# Driver.net
KiCad netlist of a schematic drawn in Altium Designer
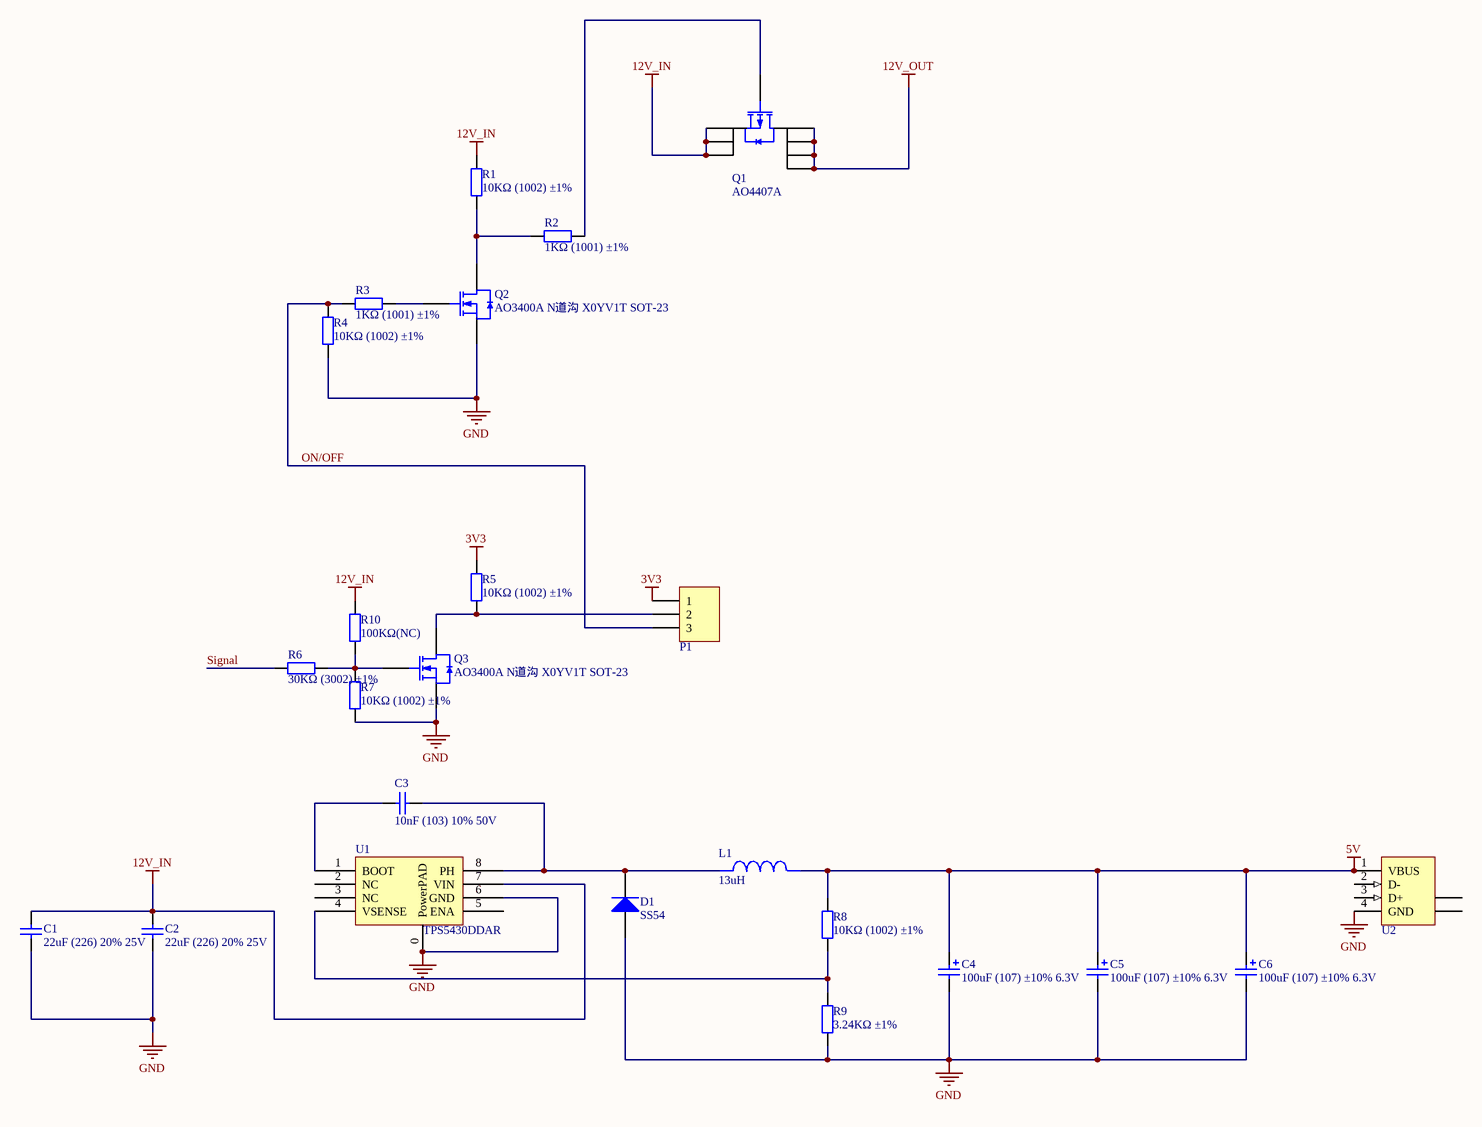
[diagram p0: Driver.SchDoc]

(export (version "E")
  (design (tool "Eeschema 10.0.6"))
  (components
    (comp (ref "C1")
      (value "22uF (226) 20% 25V")
      (footprint "0805_C")
      (description "贴片电容")
      (libsource (lib "Miscellaneous Devices LC") (part "0805 22uF (226) 20% 25V"))
    )
    (comp (ref "C2")
      (value "22uF (226) 20% 25V")
      (footprint "0805_C")
      (description "贴片电容")
      (libsource (lib "Miscellaneous Devices LC") (part "0805 22uF (226) 20% 25V"))
    )
    (comp (ref "C3")
      (value "10nF (103) 10% 50V")
      (footprint "0603_C")
      (description "贴片电容")
      (libsource (lib "Miscellaneous Devices LC") (part "0603 10nF (103) 10% 50V"))
    )
    (comp (ref "C4")
      (value "100uF (107) ±10% 6.3V")
      (footprint "CASE-B_3528")
      (description "钽电容")
      (libsource (lib "Miscellaneous Devices LC") (part "3528 100uF (107) 10% 6.3V"))
    )
    (comp (ref "C5")
      (value "100uF (107) ±10% 6.3V")
      (footprint "CASE-B_3528")
      (description "钽电容")
      (libsource (lib "Miscellaneous Devices LC") (part "3528 100uF (107) 10% 6.3V"))
    )
    (comp (ref "C6")
      (value "100uF (107) ±10% 6.3V")
      (footprint "CASE-B_3528")
      (description "钽电容")
      (libsource (lib "Miscellaneous Devices LC") (part "3528 100uF (107) 10% 6.3V"))
    )
    (comp (ref "D1")
      (value "SS54")
      (footprint "SMA(DO-214AC)_S1")
      (description "二极管")
      (libsource (lib "Miscellaneous Devices LC") (part "SMA(DO-214AC) SS54"))
    )
    (comp (ref "L1")
      (value "13uH")
      (footprint "WE-PDF-1045")
      (description "Unknown")
      (fields (field (name "MANUFACTURER PART NUMBER") "7447798131"))
      (libsource (lib "Lib") (part "7447798131"))
    )
    (comp (ref "P1")
      (value "0.1\" 3POS Header SNGL")
      (footprint "3 POS HEADER SINGLE ROW")
      (description "CONN HEADER 3POS .100\" SNGL TIN")
      (fields
        (field (name "MANUFACTURER") "Samtec Inc")
        (field (name "MANUFACTURER PART NUMBER") "TSW-150-08-T-S")
      )
      (libsource (lib "RoboteX") (part "Header 3"))
    )
    (comp (ref "Q1")
      (value "AO4407A")
      (footprint "SOIC-8_150mil")
      (description "MOS(场效应管)")
      (libsource (lib "Miscellaneous Devices LC") (part "AO4407A"))
    )
    (comp (ref "Q2")
      (value "AO3400A N道沟 X0YV1T SOT-23")
      (footprint "SOT-23-3L")
      (description "MOS(场效应管)")
      (libsource (lib "Miscellaneous Devices LC") (part "AO3400A N道沟 X0YV1T SOT-23"))
    )
    (comp (ref "Q3")
      (value "AO3400A N道沟 X0YV1T SOT-23")
      (footprint "SOT-23-3L")
      (description "MOS(场效应管)")
      (libsource (lib "Miscellaneous Devices LC") (part "AO3400A N道沟 X0YV1T SOT-23"))
    )
    (comp (ref "R1")
      (value "10KΩ (1002) ±1%")
      (footprint "0603_R")
      (description "贴片电阻")
      (libsource (lib "Miscellaneous Devices LC") (part "0603 10KΩ (1002) 1%"))
    )
    (comp (ref "R2")
      (value "1KΩ (1001) ±1%")
      (footprint "0603_R")
      (description "贴片电阻")
      (libsource (lib "Miscellaneous Devices LC") (part "0603 1KΩ (1001) 1%"))
    )
    (comp (ref "R3")
      (value "1KΩ (1001) ±1%")
      (footprint "0603_R")
      (description "贴片电阻")
      (libsource (lib "Miscellaneous Devices LC") (part "0603 1KΩ (1001) 1%"))
    )
    (comp (ref "R4")
      (value "10KΩ (1002) ±1%")
      (footprint "0603_R")
      (description "贴片电阻")
      (libsource (lib "Miscellaneous Devices LC") (part "0603 10KΩ (1002) 1%"))
    )
    (comp (ref "R5")
      (value "10KΩ (1002) ±1%")
      (footprint "0603_R")
      (description "贴片电阻")
      (libsource (lib "Miscellaneous Devices LC") (part "0603 10KΩ (1002) 1%"))
    )
    (comp (ref "R6")
      (value "30KΩ (3002) ±1%")
      (footprint "0603_R")
      (description "贴片电阻")
      (libsource (lib "Miscellaneous Devices LC") (part "0603 30KΩ (3002) 1%"))
    )
    (comp (ref "R7")
      (value "10KΩ (1002) ±1%")
      (footprint "0603_R")
      (description "贴片电阻")
      (libsource (lib "Miscellaneous Devices LC") (part "0603 10KΩ (1002) 1%"))
    )
    (comp (ref "R8")
      (value "10KΩ (1002) ±1%")
      (footprint "0603_R")
      (description "贴片电阻")
      (libsource (lib "Miscellaneous Devices LC") (part "0603 10KΩ (1002) 1%"))
    )
    (comp (ref "R9")
      (value "3.24KΩ ±1%")
      (footprint "0603_R")
      (description "贴片电阻")
      (libsource (lib "Miscellaneous Devices LC") (part "0603 3KΩ (3001) 1%"))
    )
    (comp (ref "R10")
      (value "100KΩ(NC)")
      (footprint "0603_R")
      (description "贴片电阻")
      (libsource (lib "Miscellaneous Devices LC") (part "0603 100KΩ (1003) 1%"))
    )
    (comp (ref "U1")
      (value "TPS5430DDAR")
      (footprint "SOP-8_EP_150mil")
      (description "DC-DC芯片")
      (libsource (lib "Miscellaneous Devices LC") (part "TPS5430DDAR_[C9864]"))
    )
    (comp (ref "U2")
      (value "CONN RCPT USB TYPE A R/A GOLD")
      (footprint "USB_A_RA_THRU")
      (fields
        (field (name "MANUFACTURER") "Amphenol Commercial Products")
        (field (name "MANUFACTURER PART NUMBER") "UE27AC54100")
      )
      (libsource (lib "RoboteX") (part "USB"))
    )
  )
  (nets
    (net (code "1") (name "/ON{slash}OFF") (class "Default")
      (node (ref "P1") (pin "3") (pinfunction "3_3") (pintype "passive"))
      (node (ref "R3") (pin "1") (pinfunction "1_1") (pintype "passive"))
      (node (ref "R4") (pin "2") (pinfunction "2_2") (pintype "passive"))
    )
    (net (code "2") (name "/Signal") (class "Default")
      (node (ref "R6") (pin "1") (pinfunction "1_1") (pintype "passive"))
    )
    (net (code "3") (name "3V3") (class "Default")
      (node (ref "P1") (pin "1") (pinfunction "1_1") (pintype "passive"))
      (node (ref "R5") (pin "2") (pinfunction "2_2") (pintype "passive"))
    )
    (net (code "4") (name "5V") (class "Default")
      (node (ref "C4") (pin "1") (pinfunction "1_1") (pintype "passive"))
      (node (ref "C5") (pin "1") (pinfunction "1_1") (pintype "passive"))
      (node (ref "C6") (pin "1") (pinfunction "1_1") (pintype "passive"))
      (node (ref "L1") (pin "2") (pinfunction "2_2") (pintype "passive"))
      (node (ref "R8") (pin "2") (pinfunction "2_2") (pintype "passive"))
      (node (ref "U2") (pin "1") (pinfunction "VBUS_1") (pintype "power_in"))
    )
    (net (code "5") (name "12V_IN") (class "Default")
      (node (ref "C1") (pin "2") (pinfunction "2_2") (pintype "passive"))
      (node (ref "C2") (pin "2") (pinfunction "2_2") (pintype "passive"))
      (node (ref "Q1") (pin "1") (pinfunction "S_1") (pintype "passive"))
      (node (ref "Q1") (pin "2") (pinfunction "S_2") (pintype "passive"))
      (node (ref "Q1") (pin "3") (pinfunction "S_3") (pintype "passive"))
      (node (ref "R1") (pin "2") (pinfunction "2_2") (pintype "passive"))
      (node (ref "R10") (pin "2") (pinfunction "2_2") (pintype "passive"))
      (node (ref "U1") (pin "7") (pinfunction "VIN_7") (pintype "passive"))
    )
    (net (code "6") (name "12V_OUT") (class "Default")
      (node (ref "Q1") (pin "5") (pinfunction "D_5") (pintype "passive"))
      (node (ref "Q1") (pin "6") (pinfunction "D_6") (pintype "passive"))
      (node (ref "Q1") (pin "7") (pinfunction "D_7") (pintype "passive"))
      (node (ref "Q1") (pin "8") (pinfunction "D_8") (pintype "passive"))
    )
    (net (code "7") (name "GND") (class "Default")
      (node (ref "C1") (pin "1") (pinfunction "1_1") (pintype "passive"))
      (node (ref "C2") (pin "1") (pinfunction "1_1") (pintype "passive"))
      (node (ref "C4") (pin "2") (pinfunction "2_2") (pintype "passive"))
      (node (ref "C5") (pin "2") (pinfunction "2_2") (pintype "passive"))
      (node (ref "C6") (pin "2") (pinfunction "2_2") (pintype "passive"))
      (node (ref "D1") (pin "1") (pinfunction "A_1") (pintype "passive"))
      (node (ref "Q2") (pin "2") (pinfunction "S_2") (pintype "passive"))
      (node (ref "Q3") (pin "2") (pinfunction "S_2") (pintype "passive"))
      (node (ref "R4") (pin "1") (pinfunction "1_1") (pintype "passive"))
      (node (ref "R7") (pin "1") (pinfunction "1_1") (pintype "passive"))
      (node (ref "R9") (pin "1") (pinfunction "1_1") (pintype "passive"))
      (node (ref "U1") (pin "0") (pinfunction "PowerPAD_0") (pintype "passive"))
      (node (ref "U1") (pin "6") (pinfunction "GND_6") (pintype "passive"))
      (node (ref "U2") (pin "4") (pinfunction "GND_4") (pintype "power_in"))
    )
    (net (code "8") (name "Net-(D1-K)") (class "Default")
      (node (ref "C3") (pin "1") (pinfunction "1_1") (pintype "passive"))
      (node (ref "D1") (pin "2") (pinfunction "K_2") (pintype "passive"))
      (node (ref "L1") (pin "1") (pinfunction "1_1") (pintype "passive"))
      (node (ref "U1") (pin "8") (pinfunction "PH_8") (pintype "passive"))
    )
    (net (code "9") (name "Net-(Q1-G)") (class "Default")
      (node (ref "Q1") (pin "4") (pinfunction "G_4") (pintype "passive"))
      (node (ref "R2") (pin "2") (pinfunction "2_2") (pintype "passive"))
    )
    (net (code "10") (name "Net-(Q2-D)") (class "Default")
      (node (ref "Q2") (pin "3") (pinfunction "D_3") (pintype "passive"))
      (node (ref "R1") (pin "1") (pinfunction "1_1") (pintype "passive"))
      (node (ref "R2") (pin "1") (pinfunction "1_1") (pintype "passive"))
    )
    (net (code "11") (name "Net-(Q2-G)") (class "Default")
      (node (ref "Q2") (pin "1") (pinfunction "G_1") (pintype "passive"))
      (node (ref "R3") (pin "2") (pinfunction "2_2") (pintype "passive"))
    )
    (net (code "12") (name "Net-(Q3-D)") (class "Default")
      (node (ref "P1") (pin "2") (pinfunction "2_2") (pintype "passive"))
      (node (ref "Q3") (pin "3") (pinfunction "D_3") (pintype "passive"))
      (node (ref "R5") (pin "1") (pinfunction "1_1") (pintype "passive"))
    )
    (net (code "13") (name "Net-(Q3-G)") (class "Default")
      (node (ref "Q3") (pin "1") (pinfunction "G_1") (pintype "passive"))
      (node (ref "R10") (pin "1") (pinfunction "1_1") (pintype "passive"))
      (node (ref "R6") (pin "2") (pinfunction "2_2") (pintype "passive"))
      (node (ref "R7") (pin "2") (pinfunction "2_2") (pintype "passive"))
    )
    (net (code "14") (name "Net-(U1-BOOT)") (class "Default")
      (node (ref "C3") (pin "2") (pinfunction "2_2") (pintype "passive"))
      (node (ref "U1") (pin "1") (pinfunction "BOOT_1") (pintype "passive"))
    )
    (net (code "15") (name "Net-(U1-VSENSE)") (class "Default")
      (node (ref "R8") (pin "1") (pinfunction "1_1") (pintype "passive"))
      (node (ref "R9") (pin "2") (pinfunction "2_2") (pintype "passive"))
      (node (ref "U1") (pin "4") (pinfunction "VSENSE_4") (pintype "passive"))
    )
    (net (code "16") (name "unconnected-(U1-ENA-Pad5)") (class "Default")
      (node (ref "U1") (pin "5") (pinfunction "ENA_5") (pintype "passive"))
    )
    (net (code "17") (name "unconnected-(U1-NC-Pad2)") (class "Default")
      (node (ref "U1") (pin "2") (pinfunction "NC_2") (pintype "passive"))
    )
    (net (code "18") (name "unconnected-(U1-NC-Pad3)") (class "Default")
      (node (ref "U1") (pin "3") (pinfunction "NC_3") (pintype "passive"))
    )
    (net (code "19") (name "unconnected-(U2-D+-Pad3)") (class "Default")
      (node (ref "U2") (pin "3") (pinfunction "D+_3") (pintype "input"))
    )
    (net (code "20") (name "unconnected-(U2-D--Pad2)") (class "Default")
      (node (ref "U2") (pin "2") (pinfunction "D-_2") (pintype "input"))
    )
    (net (code "21") (name "unconnected-(U2-SHLD-Pad5)") (class "Default")
      (node (ref "U2") (pin "5") (pinfunction "SHLD_5") (pintype "passive"))
    )
    (net (code "22") (name "unconnected-(U2-SHLD-Pad6)") (class "Default")
      (node (ref "U2") (pin "6") (pinfunction "SHLD_6") (pintype "passive"))
    )
  )
)
